# WheelLED_Sch.net
KiCad netlist of a schematic drawn in Altium Designer
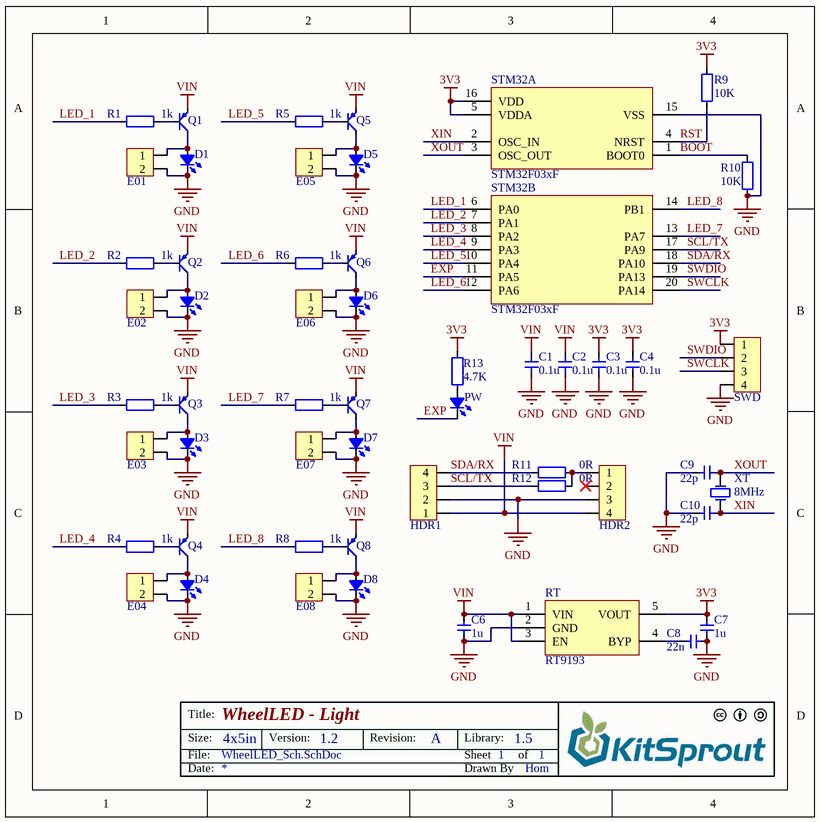
[diagram p0: WheelLED_Sch.SchDoc]

(export (version "E")
  (design (tool "Eeschema 10.0.6"))
  (components
    (comp (ref "C1")
      (value "0.1u")
      (footprint "PCB_PassiveCap:CAP_0603")
      (description "Capacitor")
      (fields (field (name "Comment") "Cap_0603"))
      (libsource (lib "SCH_Passive") (part "Cap_0603"))
    )
    (comp (ref "C2")
      (value "0.1u")
      (footprint "PCB_PassiveCap:CAP_0603")
      (description "Capacitor")
      (fields (field (name "Comment") "Cap_0603"))
      (libsource (lib "SCH_Passive") (part "Cap_0603"))
    )
    (comp (ref "C3")
      (value "0.1u")
      (footprint "PCB_PassiveCap:CAP_0603")
      (description "Capacitor")
      (fields (field (name "Comment") "Cap_0603"))
      (libsource (lib "SCH_Passive") (part "Cap_0603"))
    )
    (comp (ref "C4")
      (value "0.1u")
      (footprint "PCB_PassiveCap:CAP_0603")
      (description "Capacitor")
      (fields (field (name "Comment") "Cap_0603"))
      (libsource (lib "SCH_Passive") (part "Cap_0603"))
    )
    (comp (ref "C6")
      (value "1u")
      (footprint "PCB_PassiveCap:CAP_0603")
      (description "Capacitor")
      (fields (field (name "Comment") "Cap_0603"))
      (libsource (lib "SCH_Passive") (part "Cap_0603"))
    )
    (comp (ref "C7")
      (value "1u")
      (footprint "PCB_PassiveCap:CAP_0603")
      (description "Capacitor")
      (fields (field (name "Comment") "Cap_0603"))
      (libsource (lib "SCH_Passive") (part "Cap_0603"))
    )
    (comp (ref "C8")
      (value "22n")
      (footprint "PCB_PassiveCap:CAP_0603")
      (description "Capacitor")
      (fields (field (name "Comment") "Cap_0603"))
      (libsource (lib "SCH_Passive") (part "Cap_0603"))
    )
    (comp (ref "C9")
      (value "22p")
      (footprint "PCB_PassiveCap:CAP_0603")
      (description "Capacitor")
      (fields (field (name "Comment") "Cap_0603"))
      (libsource (lib "SCH_Passive") (part "Cap_0603"))
    )
    (comp (ref "C10")
      (value "22p")
      (footprint "PCB_PassiveCap:CAP_0603")
      (description "Capacitor")
      (fields (field (name "Comment") "Cap_0603"))
      (libsource (lib "SCH_Passive") (part "Cap_0603"))
    )
    (comp (ref "D1")
      (value "LED_5730")
      (footprint "PCB_ActiveLED:LED_5730_WHITE")
      (description "LED")
      (libsource (lib "SCH_Active") (part "LED_5730"))
    )
    (comp (ref "D2")
      (value "LED_5730")
      (footprint "PCB_ActiveLED:LED_5730_WHITE")
      (description "LED")
      (libsource (lib "SCH_Active") (part "LED_5730"))
    )
    (comp (ref "D3")
      (value "LED_5730")
      (footprint "PCB_ActiveLED:LED_5730_WHITE")
      (description "LED")
      (libsource (lib "SCH_Active") (part "LED_5730"))
    )
    (comp (ref "D4")
      (value "LED_5730")
      (footprint "PCB_ActiveLED:LED_5730_WHITE")
      (description "LED")
      (libsource (lib "SCH_Active") (part "LED_5730"))
    )
    (comp (ref "D5")
      (value "LED_5730")
      (footprint "PCB_ActiveLED:LED_5730_WHITE")
      (description "LED")
      (libsource (lib "SCH_Active") (part "LED_5730"))
    )
    (comp (ref "D6")
      (value "LED_5730")
      (footprint "PCB_ActiveLED:LED_5730_WHITE")
      (description "LED")
      (libsource (lib "SCH_Active") (part "LED_5730"))
    )
    (comp (ref "D7")
      (value "LED_5730")
      (footprint "PCB_ActiveLED:LED_5730_WHITE")
      (description "LED")
      (libsource (lib "SCH_Active") (part "LED_5730"))
    )
    (comp (ref "D8")
      (value "LED_5730")
      (footprint "PCB_ActiveLED:LED_5730_WHITE")
      (description "LED")
      (libsource (lib "SCH_Active") (part "LED_5730"))
    )
    (comp (ref "E01")
      (value "HDR1x2_2.54")
      (footprint "PCB_ConnectorHDR:HDR1X2_2.54_180H")
      (description "Header")
      (libsource (lib "SCH_ConnectorHDR") (part "HDR1x2_2.54T"))
    )
    (comp (ref "E02")
      (value "HDR1x2_2.54")
      (footprint "PCB_ConnectorHDR:HDR1X2_2.54_180H")
      (description "Header")
      (libsource (lib "SCH_ConnectorHDR") (part "HDR1x2_2.54T"))
    )
    (comp (ref "E03")
      (value "HDR1x2_2.54")
      (footprint "PCB_ConnectorHDR:HDR1X2_2.54_180H")
      (description "Header")
      (libsource (lib "SCH_ConnectorHDR") (part "HDR1x2_2.54T"))
    )
    (comp (ref "E04")
      (value "HDR1x2_2.54")
      (footprint "PCB_ConnectorHDR:HDR1X2_2.54_180H")
      (description "Header")
      (libsource (lib "SCH_ConnectorHDR") (part "HDR1x2_2.54T"))
    )
    (comp (ref "E05")
      (value "HDR1x2_2.54")
      (footprint "PCB_ConnectorHDR:HDR1X2_2.54_180H")
      (description "Header")
      (libsource (lib "SCH_ConnectorHDR") (part "HDR1x2_2.54T"))
    )
    (comp (ref "E06")
      (value "HDR1x2_2.54")
      (footprint "PCB_ConnectorHDR:HDR1X2_2.54_180H")
      (description "Header")
      (libsource (lib "SCH_ConnectorHDR") (part "HDR1x2_2.54T"))
    )
    (comp (ref "E07")
      (value "HDR1x2_2.54")
      (footprint "PCB_ConnectorHDR:HDR1X2_2.54_180H")
      (description "Header")
      (libsource (lib "SCH_ConnectorHDR") (part "HDR1x2_2.54T"))
    )
    (comp (ref "E08")
      (value "HDR1x2_2.54")
      (footprint "PCB_ConnectorHDR:HDR1X2_2.54_180H")
      (description "Header")
      (libsource (lib "SCH_ConnectorHDR") (part "HDR1x2_2.54T"))
    )
    (comp (ref "HDR1")
      (value "HDR1x4_2.54")
      (footprint "PCB_ConnectorHDR:HDR1X4_2.54_90F")
      (description "Header")
      (libsource (lib "SCH_ConnectorHDR") (part "HDR1x4_2.54"))
    )
    (comp (ref "HDR2")
      (value "HDR1x4_2.54")
      (footprint "PCB_ConnectorHDR:HDR1X4_2.54_180H")
      (description "Header")
      (libsource (lib "") (part "HDR1x4_2.54_1"))
    )
    (comp (ref "PW")
      (value "LED_0805")
      (footprint "PCB_ActiveLED:LED_0805_GREEN")
      (description "LED")
      (libsource (lib "SCH_Active") (part "LED_0805"))
    )
    (comp (ref "Q1")
      (value "BJT_PNP")
      (footprint "PCB_IntegratedCircuit:SOT23-3")
      (description "Transistor")
      (libsource (lib "SCH_Active") (part "BJT_PNP"))
    )
    (comp (ref "Q2")
      (value "BJT_PNP")
      (footprint "PCB_IntegratedCircuit:SOT23-3")
      (description "Transistor")
      (libsource (lib "SCH_Active") (part "BJT_PNP"))
    )
    (comp (ref "Q3")
      (value "BJT_PNP")
      (footprint "PCB_IntegratedCircuit:SOT23-3")
      (description "Transistor")
      (libsource (lib "SCH_Active") (part "BJT_PNP"))
    )
    (comp (ref "Q4")
      (value "BJT_PNP")
      (footprint "PCB_IntegratedCircuit:SOT23-3")
      (description "Transistor")
      (libsource (lib "SCH_Active") (part "BJT_PNP"))
    )
    (comp (ref "Q5")
      (value "BJT_PNP")
      (footprint "PCB_IntegratedCircuit:SOT23-3")
      (description "Transistor")
      (libsource (lib "SCH_Active") (part "BJT_PNP"))
    )
    (comp (ref "Q6")
      (value "BJT_PNP")
      (footprint "PCB_IntegratedCircuit:SOT23-3")
      (description "Transistor")
      (libsource (lib "SCH_Active") (part "BJT_PNP"))
    )
    (comp (ref "Q7")
      (value "BJT_PNP")
      (footprint "PCB_IntegratedCircuit:SOT23-3")
      (description "Transistor")
      (libsource (lib "SCH_Active") (part "BJT_PNP"))
    )
    (comp (ref "Q8")
      (value "BJT_PNP")
      (footprint "PCB_IntegratedCircuit:SOT23-3")
      (description "Transistor")
      (libsource (lib "SCH_Active") (part "BJT_PNP"))
    )
    (comp (ref "R1")
      (value "1k")
      (footprint "PCB_PassiveRes:RES_0603")
      (description "Resistor")
      (fields (field (name "Comment") "Res_0603"))
      (libsource (lib "SCH_Passive") (part "Res_0603"))
    )
    (comp (ref "R2")
      (value "1k")
      (footprint "PCB_PassiveRes:RES_0603")
      (description "Resistor")
      (fields (field (name "Comment") "Res_0603"))
      (libsource (lib "SCH_Passive") (part "Res_0603"))
    )
    (comp (ref "R3")
      (value "1k")
      (footprint "PCB_PassiveRes:RES_0603")
      (description "Resistor")
      (fields (field (name "Comment") "Res_0603"))
      (libsource (lib "SCH_Passive") (part "Res_0603"))
    )
    (comp (ref "R4")
      (value "1k")
      (footprint "PCB_PassiveRes:RES_0603")
      (description "Resistor")
      (fields (field (name "Comment") "Res_0603"))
      (libsource (lib "SCH_Passive") (part "Res_0603"))
    )
    (comp (ref "R5")
      (value "1k")
      (footprint "PCB_PassiveRes:RES_0603")
      (description "Resistor")
      (fields (field (name "Comment") "Res_0603"))
      (libsource (lib "SCH_Passive") (part "Res_0603"))
    )
    (comp (ref "R6")
      (value "1k")
      (footprint "PCB_PassiveRes:RES_0603")
      (description "Resistor")
      (fields (field (name "Comment") "Res_0603"))
      (libsource (lib "SCH_Passive") (part "Res_0603"))
    )
    (comp (ref "R7")
      (value "1k")
      (footprint "PCB_PassiveRes:RES_0603")
      (description "Resistor")
      (fields (field (name "Comment") "Res_0603"))
      (libsource (lib "SCH_Passive") (part "Res_0603"))
    )
    (comp (ref "R8")
      (value "1k")
      (footprint "PCB_PassiveRes:RES_0603")
      (description "Resistor")
      (fields (field (name "Comment") "Res_0603"))
      (libsource (lib "SCH_Passive") (part "Res_0603"))
    )
    (comp (ref "R9")
      (value "10K")
      (footprint "PCB_PassiveRes:RES_0603")
      (description "Resistor")
      (fields (field (name "Comment") "Res_0603"))
      (libsource (lib "") (part "Res_0603_1"))
    )
    (comp (ref "R10")
      (value "10K")
      (footprint "PCB_PassiveRes:RES_0603")
      (description "Resistor")
      (fields (field (name "Comment") "Res_0603"))
      (libsource (lib "") (part "Res_0603_1"))
    )
    (comp (ref "R11")
      (value "0R")
      (footprint "PCB_PassiveRes:RES_0603")
      (description "Resistor")
      (fields (field (name "Comment") "Res_0603"))
      (libsource (lib "SCH_Passive") (part "Res_0603"))
    )
    (comp (ref "R12")
      (value "0R")
      (footprint "PCB_PassiveRes:RES_0603")
      (description "Resistor")
      (fields (field (name "Comment") "Res_0603"))
      (libsource (lib "SCH_Passive") (part "Res_0603"))
    )
    (comp (ref "R13")
      (value "4.7K")
      (footprint "PCB_PassiveRes:RES_0805")
      (description "Resistor")
      (fields (field (name "Comment") "Res_0805"))
      (libsource (lib "SCH_Passive") (part "Res_0805"))
    )
    (comp (ref "RT")
      (value "RT9193")
      (footprint "PCB_IntegratedCircuit:SOT23-5")
      (description "Power")
      (libsource (lib "SCH_IntegratedCircuit") (part "RT9193"))
    )
    (comp (ref "STM32")
      (value "STM32F03xF")
      (footprint "PCB_IntegratedCircuit:TSSOP_E170_P0.65_20")
      (description "MCU")
      (libsource (lib "SCH_IntegratedCircuit") (part "STM32F03xF"))
    )
    (comp (ref "SWD")
      (value "HDR1x4_1.27")
      (footprint "PCB_ConnectorHDR:HDR1X4_1.27_180")
      (description "Header")
      (libsource (lib "SCH_ConnectorHDR") (part "HDR1x4_1.27"))
    )
    (comp (ref "XT")
      (value "8MHz")
      (footprint "PCB_Oscillator:XT_3225_2")
      (description "Crystal Oscillator")
      (fields (field (name "Comment") "XTAL_3225_2P"))
      (libsource (lib "SCH_Oscillator") (part "XTAL_3225_2P"))
    )
  )
  (nets
    (net (code "1") (name "/BOOT") (class "Default")
      (node (ref "R10") (pin "1") (pinfunction "1_1") (pintype "passive"))
      (node (ref "STM32") (pin "1") (pinfunction "BOOT0_1") (pintype "passive"))
    )
    (net (code "2") (name "/EXP") (class "Default")
      (node (ref "PW") (pin "2") (pinfunction "K_2") (pintype "passive"))
      (node (ref "STM32") (pin "11") (pinfunction "PA5_11") (pintype "passive"))
    )
    (net (code "3") (name "/LED_1") (class "Default")
      (node (ref "R1") (pin "1") (pinfunction "1_1") (pintype "passive"))
      (node (ref "STM32") (pin "6") (pinfunction "PA0_6") (pintype "passive"))
    )
    (net (code "4") (name "/LED_2") (class "Default")
      (node (ref "R2") (pin "1") (pinfunction "1_1") (pintype "passive"))
      (node (ref "STM32") (pin "7") (pinfunction "PA1_7") (pintype "passive"))
    )
    (net (code "5") (name "/LED_3") (class "Default")
      (node (ref "R3") (pin "1") (pinfunction "1_1") (pintype "passive"))
      (node (ref "STM32") (pin "8") (pinfunction "PA2_8") (pintype "passive"))
    )
    (net (code "6") (name "/LED_4") (class "Default")
      (node (ref "R4") (pin "1") (pinfunction "1_1") (pintype "passive"))
      (node (ref "STM32") (pin "9") (pinfunction "PA3_9") (pintype "passive"))
    )
    (net (code "7") (name "/LED_5") (class "Default")
      (node (ref "R5") (pin "1") (pinfunction "1_1") (pintype "passive"))
      (node (ref "STM32") (pin "10") (pinfunction "PA4_10") (pintype "passive"))
    )
    (net (code "8") (name "/LED_6") (class "Default")
      (node (ref "R6") (pin "1") (pinfunction "1_1") (pintype "passive"))
      (node (ref "STM32") (pin "12") (pinfunction "PA6_12") (pintype "passive"))
    )
    (net (code "9") (name "/LED_7") (class "Default")
      (node (ref "R7") (pin "1") (pinfunction "1_1") (pintype "passive"))
      (node (ref "STM32") (pin "13") (pinfunction "PA7_13") (pintype "passive"))
    )
    (net (code "10") (name "/LED_8") (class "Default")
      (node (ref "R8") (pin "1") (pinfunction "1_1") (pintype "passive"))
      (node (ref "STM32") (pin "14") (pinfunction "PB1_14") (pintype "passive"))
    )
    (net (code "11") (name "/RST") (class "Default")
      (node (ref "R9") (pin "2") (pinfunction "2_2") (pintype "passive"))
      (node (ref "STM32") (pin "4") (pinfunction "NRST_4") (pintype "passive"))
    )
    (net (code "12") (name "/SCL{slash}TX") (class "Default")
      (node (ref "HDR1") (pin "3") (pinfunction "3_3") (pintype "passive"))
      (node (ref "R12") (pin "1") (pinfunction "1_1") (pintype "passive"))
      (node (ref "STM32") (pin "17") (pinfunction "PA9_17") (pintype "passive"))
    )
    (net (code "13") (name "/SDA{slash}RX") (class "Default")
      (node (ref "HDR1") (pin "4") (pinfunction "4_4") (pintype "passive"))
      (node (ref "R11") (pin "1") (pinfunction "1_1") (pintype "passive"))
      (node (ref "STM32") (pin "18") (pinfunction "PA10_18") (pintype "passive"))
    )
    (net (code "14") (name "/SWCLK") (class "Default")
      (node (ref "STM32") (pin "20") (pinfunction "PA14_20") (pintype "passive"))
      (node (ref "SWD") (pin "3") (pinfunction "3_3") (pintype "passive"))
    )
    (net (code "15") (name "/SWDIO") (class "Default")
      (node (ref "STM32") (pin "19") (pinfunction "PA13_19") (pintype "passive"))
      (node (ref "SWD") (pin "2") (pinfunction "2_2") (pintype "passive"))
    )
    (net (code "16") (name "/XIN") (class "Default")
      (node (ref "C10") (pin "1") (pinfunction "1_1") (pintype "passive"))
      (node (ref "STM32") (pin "2") (pinfunction "OSC_IN_2") (pintype "passive"))
      (node (ref "XT") (pin "1") (pinfunction "OSC1_1") (pintype "passive"))
    )
    (net (code "17") (name "/XOUT") (class "Default")
      (node (ref "C9") (pin "1") (pinfunction "1_1") (pintype "passive"))
      (node (ref "STM32") (pin "3") (pinfunction "OSC_OUT_3") (pintype "passive"))
      (node (ref "XT") (pin "2") (pinfunction "OSC2_2") (pintype "passive"))
    )
    (net (code "18") (name "3V3") (class "Default")
      (node (ref "C3") (pin "2") (pinfunction "2_2") (pintype "passive"))
      (node (ref "C4") (pin "2") (pinfunction "2_2") (pintype "passive"))
      (node (ref "C7") (pin "2") (pinfunction "2_2") (pintype "passive"))
      (node (ref "R13") (pin "2") (pinfunction "2_2") (pintype "passive"))
      (node (ref "R9") (pin "1") (pinfunction "1_1") (pintype "passive"))
      (node (ref "RT") (pin "5") (pinfunction "VOUT_5") (pintype "passive"))
      (node (ref "STM32") (pin "16") (pinfunction "VDD_16") (pintype "passive"))
      (node (ref "STM32") (pin "5") (pinfunction "VDDA_5") (pintype "passive"))
      (node (ref "SWD") (pin "1") (pinfunction "1_1") (pintype "passive"))
    )
    (net (code "19") (name "GND") (class "Default")
      (node (ref "C1") (pin "1") (pinfunction "1_1") (pintype "passive"))
      (node (ref "C10") (pin "2") (pinfunction "2_2") (pintype "passive"))
      (node (ref "C2") (pin "1") (pinfunction "1_1") (pintype "passive"))
      (node (ref "C3") (pin "1") (pinfunction "1_1") (pintype "passive"))
      (node (ref "C4") (pin "1") (pinfunction "1_1") (pintype "passive"))
      (node (ref "C6") (pin "1") (pinfunction "1_1") (pintype "passive"))
      (node (ref "C7") (pin "1") (pinfunction "1_1") (pintype "passive"))
      (node (ref "C8") (pin "1") (pinfunction "1_1") (pintype "passive"))
      (node (ref "C9") (pin "2") (pinfunction "2_2") (pintype "passive"))
      (node (ref "D1") (pin "2") (pinfunction "K_2") (pintype "passive"))
      (node (ref "D2") (pin "2") (pinfunction "K_2") (pintype "passive"))
      (node (ref "D3") (pin "2") (pinfunction "K_2") (pintype "passive"))
      (node (ref "D4") (pin "2") (pinfunction "K_2") (pintype "passive"))
      (node (ref "D5") (pin "2") (pinfunction "K_2") (pintype "passive"))
      (node (ref "D6") (pin "2") (pinfunction "K_2") (pintype "passive"))
      (node (ref "D7") (pin "2") (pinfunction "K_2") (pintype "passive"))
      (node (ref "D8") (pin "2") (pinfunction "K_2") (pintype "passive"))
      (node (ref "E01") (pin "2") (pinfunction "2_2") (pintype "passive"))
      (node (ref "E02") (pin "2") (pinfunction "2_2") (pintype "passive"))
      (node (ref "E03") (pin "2") (pinfunction "2_2") (pintype "passive"))
      (node (ref "E04") (pin "2") (pinfunction "2_2") (pintype "passive"))
      (node (ref "E05") (pin "2") (pinfunction "2_2") (pintype "passive"))
      (node (ref "E06") (pin "2") (pinfunction "2_2") (pintype "passive"))
      (node (ref "E07") (pin "2") (pinfunction "2_2") (pintype "passive"))
      (node (ref "E08") (pin "2") (pinfunction "2_2") (pintype "passive"))
      (node (ref "HDR1") (pin "2") (pinfunction "2_2") (pintype "passive"))
      (node (ref "HDR2") (pin "3") (pinfunction "3_3") (pintype "passive"))
      (node (ref "R10") (pin "2") (pinfunction "2_2") (pintype "passive"))
      (node (ref "RT") (pin "2") (pinfunction "GND_2") (pintype "passive"))
      (node (ref "STM32") (pin "15") (pinfunction "VSS_15") (pintype "passive"))
      (node (ref "SWD") (pin "4") (pinfunction "4_4") (pintype "passive"))
    )
    (net (code "20") (name "Net-(D1-A)") (class "Default")
      (node (ref "D1") (pin "1") (pinfunction "A_1") (pintype "passive"))
      (node (ref "E01") (pin "1") (pinfunction "1_1") (pintype "passive"))
      (node (ref "Q1") (pin "3") (pinfunction "C_3") (pintype "passive"))
    )
    (net (code "21") (name "Net-(D2-A)") (class "Default")
      (node (ref "D2") (pin "1") (pinfunction "A_1") (pintype "passive"))
      (node (ref "E02") (pin "1") (pinfunction "1_1") (pintype "passive"))
      (node (ref "Q2") (pin "3") (pinfunction "C_3") (pintype "passive"))
    )
    (net (code "22") (name "Net-(D3-A)") (class "Default")
      (node (ref "D3") (pin "1") (pinfunction "A_1") (pintype "passive"))
      (node (ref "E03") (pin "1") (pinfunction "1_1") (pintype "passive"))
      (node (ref "Q3") (pin "3") (pinfunction "C_3") (pintype "passive"))
    )
    (net (code "23") (name "Net-(D4-A)") (class "Default")
      (node (ref "D4") (pin "1") (pinfunction "A_1") (pintype "passive"))
      (node (ref "E04") (pin "1") (pinfunction "1_1") (pintype "passive"))
      (node (ref "Q4") (pin "3") (pinfunction "C_3") (pintype "passive"))
    )
    (net (code "24") (name "Net-(D5-A)") (class "Default")
      (node (ref "D5") (pin "1") (pinfunction "A_1") (pintype "passive"))
      (node (ref "E05") (pin "1") (pinfunction "1_1") (pintype "passive"))
      (node (ref "Q5") (pin "3") (pinfunction "C_3") (pintype "passive"))
    )
    (net (code "25") (name "Net-(D6-A)") (class "Default")
      (node (ref "D6") (pin "1") (pinfunction "A_1") (pintype "passive"))
      (node (ref "E06") (pin "1") (pinfunction "1_1") (pintype "passive"))
      (node (ref "Q6") (pin "3") (pinfunction "C_3") (pintype "passive"))
    )
    (net (code "26") (name "Net-(D7-A)") (class "Default")
      (node (ref "D7") (pin "1") (pinfunction "A_1") (pintype "passive"))
      (node (ref "E07") (pin "1") (pinfunction "1_1") (pintype "passive"))
      (node (ref "Q7") (pin "3") (pinfunction "C_3") (pintype "passive"))
    )
    (net (code "27") (name "Net-(D8-A)") (class "Default")
      (node (ref "D8") (pin "1") (pinfunction "A_1") (pintype "passive"))
      (node (ref "E08") (pin "1") (pinfunction "1_1") (pintype "passive"))
      (node (ref "Q8") (pin "3") (pinfunction "C_3") (pintype "passive"))
    )
    (net (code "28") (name "Net-(HDR2-Pad1)") (class "Default")
      (node (ref "HDR2") (pin "1") (pinfunction "1_1") (pintype "passive"))
      (node (ref "R11") (pin "2") (pinfunction "2_2") (pintype "passive"))
      (node (ref "R12") (pin "2") (pinfunction "2_2") (pintype "passive"))
    )
    (net (code "29") (name "Net-(PW-A)") (class "Default")
      (node (ref "PW") (pin "1") (pinfunction "A_1") (pintype "passive"))
      (node (ref "R13") (pin "1") (pinfunction "1_1") (pintype "passive"))
    )
    (net (code "30") (name "Net-(Q1-B)") (class "Default")
      (node (ref "Q1") (pin "1") (pinfunction "B_1") (pintype "passive"))
      (node (ref "R1") (pin "2") (pinfunction "2_2") (pintype "passive"))
    )
    (net (code "31") (name "Net-(Q2-B)") (class "Default")
      (node (ref "Q2") (pin "1") (pinfunction "B_1") (pintype "passive"))
      (node (ref "R2") (pin "2") (pinfunction "2_2") (pintype "passive"))
    )
    (net (code "32") (name "Net-(Q3-B)") (class "Default")
      (node (ref "Q3") (pin "1") (pinfunction "B_1") (pintype "passive"))
      (node (ref "R3") (pin "2") (pinfunction "2_2") (pintype "passive"))
    )
    (net (code "33") (name "Net-(Q4-B)") (class "Default")
      (node (ref "Q4") (pin "1") (pinfunction "B_1") (pintype "passive"))
      (node (ref "R4") (pin "2") (pinfunction "2_2") (pintype "passive"))
    )
    (net (code "34") (name "Net-(Q5-B)") (class "Default")
      (node (ref "Q5") (pin "1") (pinfunction "B_1") (pintype "passive"))
      (node (ref "R5") (pin "2") (pinfunction "2_2") (pintype "passive"))
    )
    (net (code "35") (name "Net-(Q6-B)") (class "Default")
      (node (ref "Q6") (pin "1") (pinfunction "B_1") (pintype "passive"))
      (node (ref "R6") (pin "2") (pinfunction "2_2") (pintype "passive"))
    )
    (net (code "36") (name "Net-(Q7-B)") (class "Default")
      (node (ref "Q7") (pin "1") (pinfunction "B_1") (pintype "passive"))
      (node (ref "R7") (pin "2") (pinfunction "2_2") (pintype "passive"))
    )
    (net (code "37") (name "Net-(Q8-B)") (class "Default")
      (node (ref "Q8") (pin "1") (pinfunction "B_1") (pintype "passive"))
      (node (ref "R8") (pin "2") (pinfunction "2_2") (pintype "passive"))
    )
    (net (code "38") (name "Net-(RT-BYP)") (class "Default")
      (node (ref "C8") (pin "2") (pinfunction "2_2") (pintype "passive"))
      (node (ref "RT") (pin "4") (pinfunction "BYP_4") (pintype "passive"))
    )
    (net (code "39") (name "VIN") (class "Default")
      (node (ref "C1") (pin "2") (pinfunction "2_2") (pintype "passive"))
      (node (ref "C2") (pin "2") (pinfunction "2_2") (pintype "passive"))
      (node (ref "C6") (pin "2") (pinfunction "2_2") (pintype "passive"))
      (node (ref "HDR1") (pin "1") (pinfunction "1_1") (pintype "passive"))
      (node (ref "HDR2") (pin "4") (pinfunction "4_4") (pintype "passive"))
      (node (ref "Q1") (pin "2") (pinfunction "E_2") (pintype "passive"))
      (node (ref "Q2") (pin "2") (pinfunction "E_2") (pintype "passive"))
      (node (ref "Q3") (pin "2") (pinfunction "E_2") (pintype "passive"))
      (node (ref "Q4") (pin "2") (pinfunction "E_2") (pintype "passive"))
      (node (ref "Q5") (pin "2") (pinfunction "E_2") (pintype "passive"))
      (node (ref "Q6") (pin "2") (pinfunction "E_2") (pintype "passive"))
      (node (ref "Q7") (pin "2") (pinfunction "E_2") (pintype "passive"))
      (node (ref "Q8") (pin "2") (pinfunction "E_2") (pintype "passive"))
      (node (ref "RT") (pin "1") (pinfunction "VIN_1") (pintype "passive"))
      (node (ref "RT") (pin "3") (pinfunction "EN_3") (pintype "power_in"))
    )
    (net (code "40") (name "unconnected-(HDR2-Pad2)") (class "Default")
      (node (ref "HDR2") (pin "2") (pinfunction "2_2") (pintype "passive+no_connect"))
    )
  )
)
